# RX5808_BUT.net
KiCad netlist of a schematic drawn in Altium Designer
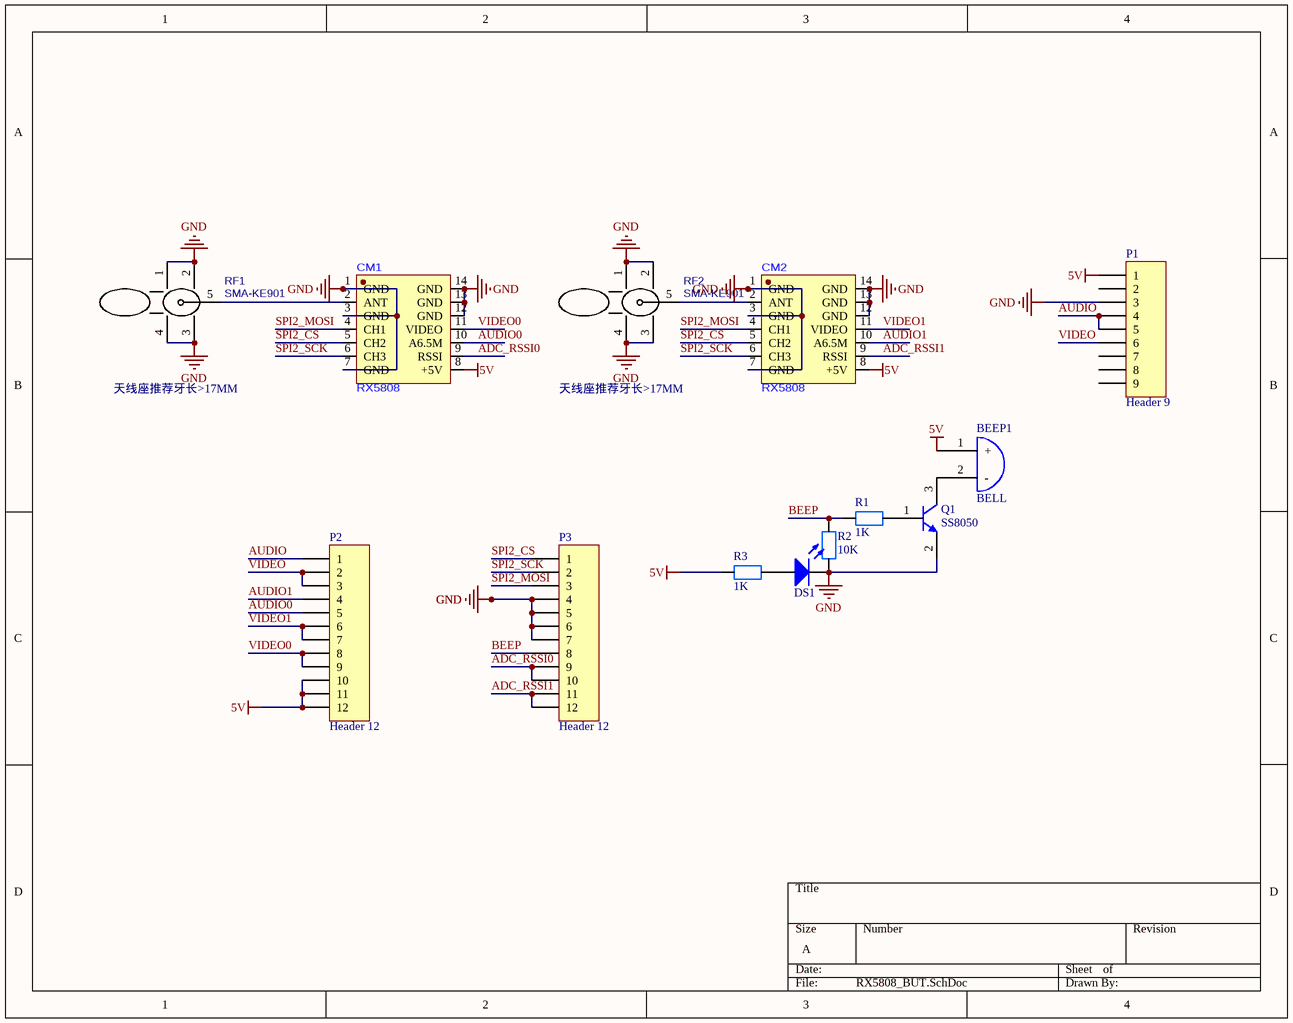
[diagram p0: RX5808_BUT.SchDoc]

(export (version "E")
  (design (tool "Eeschema 10.0.6"))
  (components
    (comp (ref "BEEP1")
      (value "BELL")
      (footprint "BEEP 5x9x5.5")
      (description "蜂鸣器")
      (libsource (lib "My Library") (part "Beep"))
    )
    (comp (ref "CM1")
      (value "RX5808")
      (footprint "COMM-SMD_12P_RX5808")
      (libsource (lib "My Library") (part "RX5808"))
    )
    (comp (ref "CM2")
      (value "RX5808")
      (footprint "COMM-SMD_12P_RX5808")
      (libsource (lib "My Library") (part "RX5808"))
    )
    (comp (ref "DS1") (value "LED") (footprint "0402_LED") (libsource (lib "My Library") (part "LED")))
    (comp (ref "P1")
      (value "Header 9")
      (footprint "HDR-1X9")
      (description "Header, 9-Pin")
      (fields (field (name "PUBLISHER") "Altium Limited"))
      (libsource (lib "Connectors") (part "Header 9"))
    )
    (comp (ref "P2")
      (value "Header 12")
      (footprint "HDR1.27-1x12-M")
      (description "Header, 12-Pin")
      (fields (field (name "PUBLISHER") "Altium Limited"))
      (libsource (lib "Connectors") (part "Header 12"))
    )
    (comp (ref "P3")
      (value "Header 12")
      (footprint "HDR1.27-1x12-M")
      (description "Header, 12-Pin")
      (fields (field (name "PUBLISHER") "Altium Limited"))
      (libsource (lib "Connectors") (part "Header 12"))
    )
    (comp (ref "Q1")
      (value "SS8050")
      (footprint "SOT23A")
      (description "NPN三极管")
      (libsource (lib "My Library") (part "SS8050"))
    )
    (comp (ref "R1")
      (value "1K")
      (footprint "0402_RES")
      (description "电阻")
      (libsource (lib "My Library") (part "RES"))
    )
    (comp (ref "R2")
      (value "10K")
      (footprint "0402_RES")
      (description "电阻")
      (libsource (lib "My Library") (part "RES"))
    )
    (comp (ref "R3")
      (value "1K")
      (footprint "0402_RES")
      (description "电阻")
      (libsource (lib "My Library") (part "RES"))
    )
    (comp (ref "RF1")
      (value "SMA-KE901")
      (footprint "SMA-TH_SMA-KE901")
      (fields (field (name "BOM_SUPPLIER PART") "C914559") (field (name "CONTRIBUTOR") "LCSC"))
      (libsource (lib "My Library") (part "SMA-KE901"))
    )
    (comp (ref "RF2")
      (value "SMA-KE901")
      (footprint "SMA-TH_SMA-KE901")
      (fields (field (name "BOM_SUPPLIER PART") "C914559") (field (name "CONTRIBUTOR") "LCSC"))
      (libsource (lib "My Library") (part "SMA-KE901"))
    )
  )
  (nets
    (net (code "1") (name "/ADC_RSSI0") (class "Default")
      (node (ref "CM1") (pin "9") (pinfunction "RSSI_9") (pintype "passive"))
      (node (ref "P3") (pin "10") (pinfunction "10_10") (pintype "passive"))
      (node (ref "P3") (pin "9") (pinfunction "9_9") (pintype "passive"))
    )
    (net (code "2") (name "/ADC_RSSI1") (class "Default")
      (node (ref "CM2") (pin "9") (pinfunction "RSSI_9") (pintype "passive"))
      (node (ref "P3") (pin "11") (pinfunction "11_11") (pintype "passive"))
      (node (ref "P3") (pin "12") (pinfunction "12_12") (pintype "passive"))
    )
    (net (code "3") (name "/AUDIO") (class "Default")
      (node (ref "P1") (pin "4") (pinfunction "4_4") (pintype "passive"))
      (node (ref "P1") (pin "5") (pinfunction "5_5") (pintype "passive"))
      (node (ref "P2") (pin "1") (pinfunction "1_1") (pintype "passive"))
    )
    (net (code "4") (name "/AUDIO0") (class "Default")
      (node (ref "CM1") (pin "10") (pinfunction "A6.5M_10") (pintype "passive"))
      (node (ref "P2") (pin "5") (pinfunction "5_5") (pintype "passive"))
    )
    (net (code "5") (name "/AUDIO1") (class "Default")
      (node (ref "CM2") (pin "10") (pinfunction "A6.5M_10") (pintype "passive"))
      (node (ref "P2") (pin "4") (pinfunction "4_4") (pintype "passive"))
    )
    (net (code "6") (name "/BEEP") (class "Default")
      (node (ref "P3") (pin "8") (pinfunction "8_8") (pintype "passive"))
      (node (ref "R1") (pin "1") (pinfunction "1_1") (pintype "passive"))
      (node (ref "R2") (pin "2") (pinfunction "2_2") (pintype "passive"))
    )
    (net (code "7") (name "/SPI2_CS") (class "Default")
      (node (ref "CM1") (pin "5") (pinfunction "CH2_5") (pintype "passive"))
      (node (ref "CM2") (pin "5") (pinfunction "CH2_5") (pintype "passive"))
      (node (ref "P3") (pin "1") (pinfunction "1_1") (pintype "passive"))
    )
    (net (code "8") (name "/SPI2_MOSI") (class "Default")
      (node (ref "CM1") (pin "4") (pinfunction "CH1_4") (pintype "passive"))
      (node (ref "CM2") (pin "4") (pinfunction "CH1_4") (pintype "passive"))
      (node (ref "P3") (pin "3") (pinfunction "3_3") (pintype "passive"))
    )
    (net (code "9") (name "/SPI2_SCK") (class "Default")
      (node (ref "CM1") (pin "6") (pinfunction "CH3_6") (pintype "passive"))
      (node (ref "CM2") (pin "6") (pinfunction "CH3_6") (pintype "passive"))
      (node (ref "P3") (pin "2") (pinfunction "2_2") (pintype "passive"))
    )
    (net (code "10") (name "/VIDEO") (class "Default")
      (node (ref "P1") (pin "6") (pinfunction "6_6") (pintype "passive"))
      (node (ref "P2") (pin "2") (pinfunction "2_2") (pintype "passive"))
      (node (ref "P2") (pin "3") (pinfunction "3_3") (pintype "passive"))
    )
    (net (code "11") (name "/VIDEO0") (class "Default")
      (node (ref "CM1") (pin "11") (pinfunction "VIDEO_11") (pintype "passive"))
      (node (ref "P2") (pin "8") (pinfunction "8_8") (pintype "passive"))
      (node (ref "P2") (pin "9") (pinfunction "9_9") (pintype "passive"))
    )
    (net (code "12") (name "/VIDEO1") (class "Default")
      (node (ref "CM2") (pin "11") (pinfunction "VIDEO_11") (pintype "passive"))
      (node (ref "P2") (pin "6") (pinfunction "6_6") (pintype "passive"))
      (node (ref "P2") (pin "7") (pinfunction "7_7") (pintype "passive"))
    )
    (net (code "13") (name "5V") (class "Default")
      (node (ref "BEEP1") (pin "1") (pinfunction "+_1") (pintype "passive"))
      (node (ref "CM1") (pin "8") (pinfunction "+5V_8") (pintype "passive"))
      (node (ref "CM2") (pin "8") (pinfunction "+5V_8") (pintype "passive"))
      (node (ref "P1") (pin "1") (pinfunction "1_1") (pintype "passive"))
      (node (ref "P2") (pin "10") (pinfunction "10_10") (pintype "passive"))
      (node (ref "P2") (pin "11") (pinfunction "11_11") (pintype "passive"))
      (node (ref "P2") (pin "12") (pinfunction "12_12") (pintype "passive"))
      (node (ref "R3") (pin "1") (pinfunction "1_1") (pintype "passive"))
    )
    (net (code "14") (name "GND") (class "Default")
      (node (ref "CM1") (pin "1") (pinfunction "GND_1") (pintype "passive"))
      (node (ref "CM1") (pin "12") (pinfunction "GND_12") (pintype "passive"))
      (node (ref "CM1") (pin "13") (pinfunction "GND_13") (pintype "passive"))
      (node (ref "CM1") (pin "14") (pinfunction "GND_14") (pintype "passive"))
      (node (ref "CM1") (pin "3") (pinfunction "GND_3") (pintype "passive"))
      (node (ref "CM1") (pin "7") (pinfunction "GND_7") (pintype "passive"))
      (node (ref "CM2") (pin "1") (pinfunction "GND_1") (pintype "passive"))
      (node (ref "CM2") (pin "12") (pinfunction "GND_12") (pintype "passive"))
      (node (ref "CM2") (pin "13") (pinfunction "GND_13") (pintype "passive"))
      (node (ref "CM2") (pin "14") (pinfunction "GND_14") (pintype "passive"))
      (node (ref "CM2") (pin "3") (pinfunction "GND_3") (pintype "passive"))
      (node (ref "CM2") (pin "7") (pinfunction "GND_7") (pintype "passive"))
      (node (ref "DS1") (pin "2") (pinfunction "K_2") (pintype "passive"))
      (node (ref "P1") (pin "3") (pinfunction "3_3") (pintype "passive"))
      (node (ref "P3") (pin "4") (pinfunction "4_4") (pintype "passive"))
      (node (ref "P3") (pin "5") (pinfunction "5_5") (pintype "passive"))
      (node (ref "P3") (pin "6") (pinfunction "6_6") (pintype "passive"))
      (node (ref "P3") (pin "7") (pinfunction "7_7") (pintype "passive"))
      (node (ref "Q1") (pin "2") (pinfunction "E_2") (pintype "passive"))
      (node (ref "R2") (pin "1") (pinfunction "1_1") (pintype "passive"))
      (node (ref "RF1") (pin "1") (pinfunction "1_1") (pintype "passive"))
      (node (ref "RF1") (pin "2") (pinfunction "2_2") (pintype "passive"))
      (node (ref "RF1") (pin "3") (pinfunction "3_3") (pintype "passive"))
      (node (ref "RF1") (pin "4") (pinfunction "4_4") (pintype "passive"))
      (node (ref "RF2") (pin "1") (pinfunction "1_1") (pintype "passive"))
      (node (ref "RF2") (pin "2") (pinfunction "2_2") (pintype "passive"))
      (node (ref "RF2") (pin "3") (pinfunction "3_3") (pintype "passive"))
      (node (ref "RF2") (pin "4") (pinfunction "4_4") (pintype "passive"))
    )
    (net (code "15") (name "Net-(BEEP1--)") (class "Default")
      (node (ref "BEEP1") (pin "2") (pinfunction "-_2") (pintype "passive"))
      (node (ref "Q1") (pin "3") (pinfunction "C_3") (pintype "passive"))
    )
    (net (code "16") (name "Net-(CM1-ANT)") (class "Default")
      (node (ref "CM1") (pin "2") (pinfunction "ANT_2") (pintype "passive"))
      (node (ref "RF1") (pin "5") (pinfunction "5_5") (pintype "passive"))
    )
    (net (code "17") (name "Net-(CM2-ANT)") (class "Default")
      (node (ref "CM2") (pin "2") (pinfunction "ANT_2") (pintype "passive"))
      (node (ref "RF2") (pin "5") (pinfunction "5_5") (pintype "passive"))
    )
    (net (code "18") (name "Net-(DS1-A)") (class "Default")
      (node (ref "DS1") (pin "1") (pinfunction "A_1") (pintype "passive"))
      (node (ref "R3") (pin "2") (pinfunction "2_2") (pintype "passive"))
    )
    (net (code "19") (name "Net-(Q1-B)") (class "Default")
      (node (ref "Q1") (pin "1") (pinfunction "B_1") (pintype "passive"))
      (node (ref "R1") (pin "2") (pinfunction "2_2") (pintype "passive"))
    )
    (net (code "20") (name "unconnected-(P1-Pad2)") (class "Default")
      (node (ref "P1") (pin "2") (pinfunction "2_2") (pintype "passive"))
    )
    (net (code "21") (name "unconnected-(P1-Pad7)") (class "Default")
      (node (ref "P1") (pin "7") (pinfunction "7_7") (pintype "passive"))
    )
    (net (code "22") (name "unconnected-(P1-Pad8)") (class "Default")
      (node (ref "P1") (pin "8") (pinfunction "8_8") (pintype "passive"))
    )
    (net (code "23") (name "unconnected-(P1-Pad9)") (class "Default")
      (node (ref "P1") (pin "9") (pinfunction "9_9") (pintype "passive"))
    )
  )
)
